# main.net
KiCad netlist of a schematic drawn in EAGLE
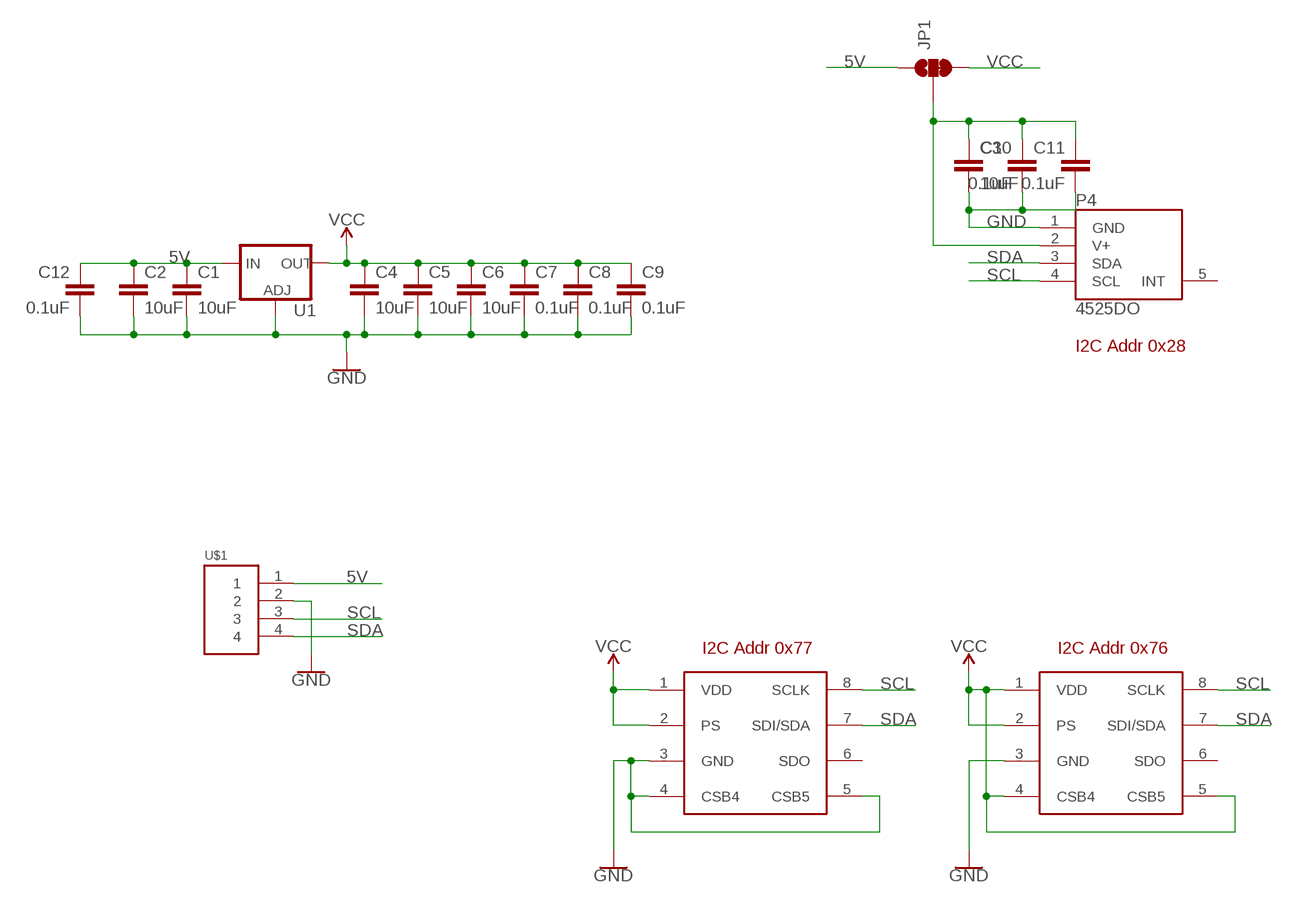
[diagram p0: schematic, sheet 1]

(export (version "E")
  (design (tool "Eeschema 10.0.6"))
  (components
    (comp (ref "C1")
      (value "10uF")
      (footprint "eagle-import:0805")
      (libsource (lib "eagle-import") (part "10UF-0805-10V-10%"))
    )
    (comp (ref "C2")
      (value "10uF")
      (footprint "eagle-import:0805")
      (libsource (lib "eagle-import") (part "10UF-0805-10V-10%"))
    )
    (comp (ref "C3")
      (value "10uF")
      (footprint "eagle-import:0805")
      (libsource (lib "eagle-import") (part "10UF-0805-10V-10%"))
    )
    (comp (ref "C4")
      (value "10uF")
      (footprint "eagle-import:0805")
      (libsource (lib "eagle-import") (part "10UF-0805-10V-10%"))
    )
    (comp (ref "C5")
      (value "10uF")
      (footprint "eagle-import:0805")
      (libsource (lib "eagle-import") (part "10UF-0805-10V-10%"))
    )
    (comp (ref "C6")
      (value "10uF")
      (footprint "eagle-import:0805")
      (libsource (lib "eagle-import") (part "10UF-0805-10V-10%"))
    )
    (comp (ref "C7")
      (value "0.1uF")
      (footprint "eagle-import:0603")
      (libsource (lib "eagle-import") (part "0.1UF-0603-25V-5%"))
    )
    (comp (ref "C8")
      (value "0.1uF")
      (footprint "eagle-import:0603")
      (libsource (lib "eagle-import") (part "0.1UF-0603-25V-5%"))
    )
    (comp (ref "C9")
      (value "0.1uF")
      (footprint "eagle-import:0603")
      (libsource (lib "eagle-import") (part "0.1UF-0603-25V-5%"))
    )
    (comp (ref "C10")
      (value "0.1uF")
      (footprint "eagle-import:0603")
      (libsource (lib "eagle-import") (part "0.1UF-0603-25V-5%"))
    )
    (comp (ref "C11")
      (value "0.1uF")
      (footprint "eagle-import:0603")
      (libsource (lib "eagle-import") (part "0.1UF-0603-25V-5%"))
    )
    (comp (ref "C12")
      (value "0.1uF")
      (footprint "eagle-import:0603")
      (libsource (lib "eagle-import") (part "0.1UF-0603-25V-5%"))
    )
    (comp (ref "JP1")
      (value "JUMPER-SMT_3_1-NC_TRACE_NO-SILK")
      (footprint "eagle-import:SMT-JUMPER_3_1-NC_TRACE_NO-SILK")
      (libsource (lib "eagle-import") (part "JUMPER-SMT_3_1-NC_TRACE_NO-SILK"))
    )
    (comp (ref "P1")
      (value "MS5611")
      (footprint "eagle-import:MS5611")
      (libsource (lib "eagle-import") (part "MS5611"))
    )
    (comp (ref "P2")
      (value "MS5611")
      (footprint "eagle-import:MS5611")
      (libsource (lib "eagle-import") (part "MS5611"))
    )
    (comp (ref "P4")
      (value "4525DO")
      (footprint "eagle-import:DIP1270W53P254L990H762Q8B")
      (libsource (lib "eagle-import") (part "MS4525MS4525DO"))
    )
    (comp (ref "U$1")
      (value "HEADER4VALULOK")
      (footprint "eagle-import:4PINVALULOK")
      (libsource (lib "eagle-import") (part "HEADER4VALULOK"))
    )
    (comp (ref "U1")
      (value "V_REG_317SMD")
      (footprint "eagle-import:SOT223")
      (libsource (lib "eagle-import") (part "V_REG_317SMD"))
    )
  )
  (nets
    (net (code "1") (name "/5V") (class "Default")
      (node (ref "C1") (pin "1") (pinfunction "1_1") (pintype "passive"))
      (node (ref "C12") (pin "1") (pinfunction "1_1") (pintype "passive"))
      (node (ref "C2") (pin "1") (pinfunction "1_1") (pintype "passive"))
      (node (ref "JP1") (pin "1") (pinfunction "1_1") (pintype "passive"))
      (node (ref "U$1") (pin "1") (pinfunction "1_1") (pintype "bidirectional"))
      (node (ref "U1") (pin "3") (pinfunction "IN_3") (pintype "input"))
    )
    (net (code "2") (name "/SCL") (class "Default")
      (node (ref "P1") (pin "8") (pinfunction "SCLK_8") (pintype "bidirectional"))
      (node (ref "P2") (pin "8") (pinfunction "SCLK_8") (pintype "bidirectional"))
      (node (ref "P4") (pin "4") (pinfunction "SCL_4") (pintype "bidirectional"))
      (node (ref "U$1") (pin "3") (pinfunction "3_3") (pintype "bidirectional"))
    )
    (net (code "3") (name "/SDA") (class "Default")
      (node (ref "P1") (pin "7") (pinfunction "SDI/SDA_7") (pintype "bidirectional"))
      (node (ref "P2") (pin "7") (pinfunction "SDI/SDA_7") (pintype "bidirectional"))
      (node (ref "P4") (pin "3") (pinfunction "SDA_3") (pintype "bidirectional"))
      (node (ref "U$1") (pin "4") (pinfunction "4_4") (pintype "bidirectional"))
    )
    (net (code "4") (name "GND") (class "Default")
      (node (ref "C1") (pin "2") (pinfunction "2_2") (pintype "passive"))
      (node (ref "C10") (pin "2") (pinfunction "2_2") (pintype "passive"))
      (node (ref "C11") (pin "2") (pinfunction "2_2") (pintype "passive"))
      (node (ref "C12") (pin "2") (pinfunction "2_2") (pintype "passive"))
      (node (ref "C2") (pin "2") (pinfunction "2_2") (pintype "passive"))
      (node (ref "C3") (pin "2") (pinfunction "2_2") (pintype "passive"))
      (node (ref "C4") (pin "2") (pinfunction "2_2") (pintype "passive"))
      (node (ref "C5") (pin "2") (pinfunction "2_2") (pintype "passive"))
      (node (ref "C6") (pin "2") (pinfunction "2_2") (pintype "passive"))
      (node (ref "C7") (pin "2") (pinfunction "2_2") (pintype "passive"))
      (node (ref "C8") (pin "2") (pinfunction "2_2") (pintype "passive"))
      (node (ref "C9") (pin "2") (pinfunction "2_2") (pintype "passive"))
      (node (ref "P1") (pin "3") (pinfunction "GND_3") (pintype "bidirectional"))
      (node (ref "P1") (pin "4") (pinfunction "CSB4_4") (pintype "bidirectional"))
      (node (ref "P1") (pin "5") (pinfunction "CSB5_5") (pintype "bidirectional"))
      (node (ref "P2") (pin "3") (pinfunction "GND_3") (pintype "bidirectional"))
      (node (ref "P4") (pin "1") (pinfunction "GND_1") (pintype "bidirectional"))
      (node (ref "U$1") (pin "2") (pinfunction "2_2") (pintype "bidirectional"))
      (node (ref "U1") (pin "1") (pinfunction "ADJ_1") (pintype "input"))
    )
    (net (code "5") (name "Net-(P4-V+)") (class "Default")
      (node (ref "C10") (pin "1") (pinfunction "1_1") (pintype "passive"))
      (node (ref "C11") (pin "1") (pinfunction "1_1") (pintype "passive"))
      (node (ref "C3") (pin "1") (pinfunction "1_1") (pintype "passive"))
      (node (ref "JP1") (pin "2") (pinfunction "2_2") (pintype "passive"))
      (node (ref "P4") (pin "2") (pinfunction "V+_2") (pintype "bidirectional"))
    )
    (net (code "6") (name "VCC") (class "Default")
      (node (ref "C4") (pin "1") (pinfunction "1_1") (pintype "passive"))
      (node (ref "C5") (pin "1") (pinfunction "1_1") (pintype "passive"))
      (node (ref "C6") (pin "1") (pinfunction "1_1") (pintype "passive"))
      (node (ref "C7") (pin "1") (pinfunction "1_1") (pintype "passive"))
      (node (ref "C8") (pin "1") (pinfunction "1_1") (pintype "passive"))
      (node (ref "C9") (pin "1") (pinfunction "1_1") (pintype "passive"))
      (node (ref "JP1") (pin "3") (pinfunction "3_3") (pintype "passive"))
      (node (ref "P1") (pin "1") (pinfunction "VDD_1") (pintype "bidirectional"))
      (node (ref "P1") (pin "2") (pinfunction "PS_2") (pintype "bidirectional"))
      (node (ref "P2") (pin "1") (pinfunction "VDD_1") (pintype "bidirectional"))
      (node (ref "P2") (pin "2") (pinfunction "PS_2") (pintype "bidirectional"))
      (node (ref "P2") (pin "4") (pinfunction "CSB4_4") (pintype "bidirectional"))
      (node (ref "P2") (pin "5") (pinfunction "CSB5_5") (pintype "bidirectional"))
      (node (ref "U1") (pin "2") (pinfunction "OUT_2") (pintype "output"))
    )
    (net (code "7") (name "unconnected-(P1-SDO-Pad6)") (class "Default")
      (node (ref "P1") (pin "6") (pinfunction "SDO_6") (pintype "bidirectional"))
    )
    (net (code "8") (name "unconnected-(P2-SDO-Pad6)") (class "Default")
      (node (ref "P2") (pin "6") (pinfunction "SDO_6") (pintype "bidirectional"))
    )
    (net (code "9") (name "unconnected-(P4-INT-Pad5)") (class "Default")
      (node (ref "P4") (pin "5") (pinfunction "INT_5") (pintype "bidirectional"))
    )
  )
)
